# ArduinoRgbController.net
KiCad netlist of a schematic drawn in EAGLE
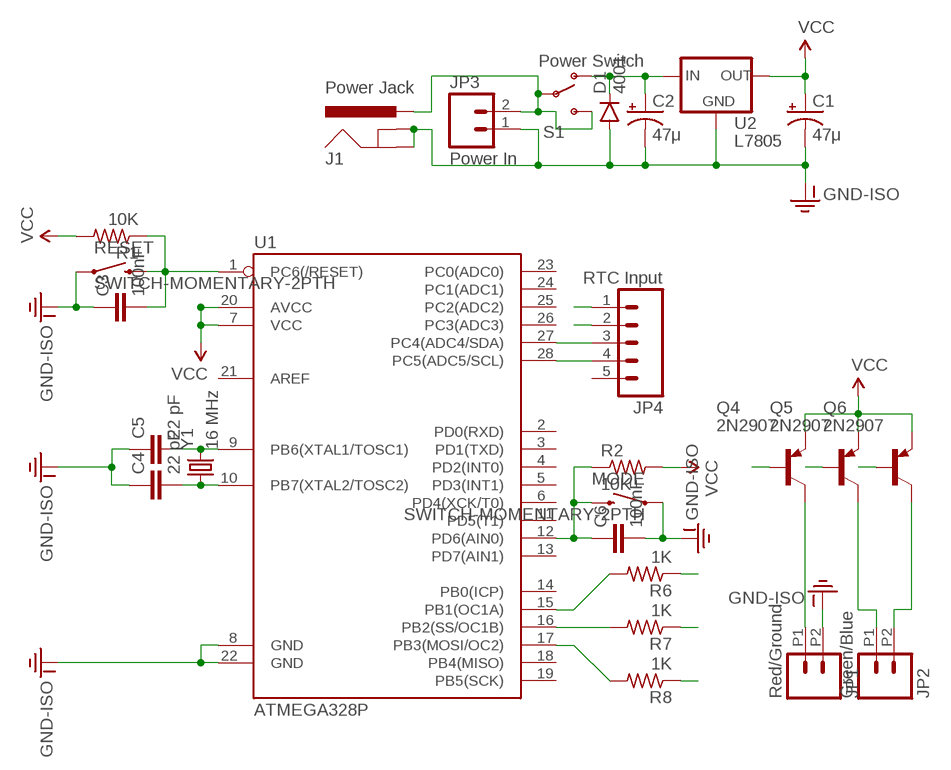
[diagram p0: schematic, sheet 1]

(export (version "E")
  (design (tool "Eeschema 10.0.6"))
  (components
    (comp (ref "C1")
      (value "47μ")
      (footprint "eagle-import:ELECTROLYTIC_CAP")
      (libsource (lib "eagle-import") (part "ELECTROLYTIC_CAP2.54MM"))
    )
    (comp (ref "C2")
      (value "47μ")
      (footprint "eagle-import:ELECTROLYTIC_CAP")
      (libsource (lib "eagle-import") (part "ELECTROLYTIC_CAP2.54MM"))
    )
    (comp (ref "C3")
      (value "100nF")
      (footprint "eagle-import:CAP-PTH-SMALL")
      (libsource (lib "eagle-import") (part "CAPPTH"))
    )
    (comp (ref "C4")
      (value "22 pF")
      (footprint "eagle-import:CAP-PTH-SMALL")
      (libsource (lib "eagle-import") (part "CAPPTH"))
    )
    (comp (ref "C5")
      (value "22 pF")
      (footprint "eagle-import:CAP-PTH-SMALL")
      (libsource (lib "eagle-import") (part "CAPPTH"))
    )
    (comp (ref "C6")
      (value "100nF")
      (footprint "eagle-import:CAP-PTH-SMALL")
      (libsource (lib "eagle-import") (part "CAPPTH"))
    )
    (comp (ref "D1")
      (value "4001")
      (footprint "eagle-import:DIODE-1N4001")
      (libsource (lib "eagle-import") (part "DIODEPTH"))
    )
    (comp (ref "J1")
      (value "Power Jack")
      (footprint "eagle-import:POWER_JACK")
      (libsource (lib "eagle-import") (part "POWER_JACK{dblquote}"))
    )
    (comp (ref "JP1")
      (value "Red/Ground")
      (footprint "eagle-import:1X02_2.54_SCREWTERM")
      (libsource (lib "eagle-import") (part "M022.54MM_SCREWTERM"))
    )
    (comp (ref "JP2")
      (value "Green/Blue")
      (footprint "eagle-import:1X02_2.54_SCREWTERM")
      (libsource (lib "eagle-import") (part "M022.54MM_SCREWTERM"))
    )
    (comp (ref "JP3")
      (value "Power In")
      (footprint "eagle-import:SCREWTERMINAL-5MM-2")
      (libsource (lib "eagle-import") (part "M025MM"))
    )
    (comp (ref "JP4")
      (value "RTC Input")
      (footprint "eagle-import:1X05_LONGPADS")
      (libsource (lib "eagle-import") (part "M05PTH_LONGPADS"))
    )
    (comp (ref "MODE")
      (value "SWITCH-MOMENTARY-2PTH")
      (footprint "eagle-import:TACTILE-PTH")
      (libsource (lib "eagle-import") (part "SWITCH-MOMENTARY-2PTH"))
    )
    (comp (ref "Q4")
      (value "2N2907")
      (footprint "eagle-import:TO92-EBC-OVAL")
      (libsource (lib "eagle-import") (part "2N2907"))
    )
    (comp (ref "Q5")
      (value "2N2907")
      (footprint "eagle-import:TO92-EBC-OVAL")
      (libsource (lib "eagle-import") (part "2N2907"))
    )
    (comp (ref "Q6")
      (value "2N2907")
      (footprint "eagle-import:TO92-EBC-OVAL")
      (libsource (lib "eagle-import") (part "2N2907"))
    )
    (comp (ref "R1")
      (value "10K")
      (footprint "eagle-import:0207_9")
      (libsource (lib "eagle-import") (part "R-US_0207/9"))
    )
    (comp (ref "R2")
      (value "10K")
      (footprint "eagle-import:0207_9")
      (libsource (lib "eagle-import") (part "R-US_0207/9"))
    )
    (comp (ref "R6")
      (value "1K")
      (footprint "eagle-import:0207_9")
      (libsource (lib "eagle-import") (part "R-US_0207/9"))
    )
    (comp (ref "R7")
      (value "1K")
      (footprint "eagle-import:0207_9")
      (libsource (lib "eagle-import") (part "R-US_0207/9"))
    )
    (comp (ref "R8")
      (value "1K")
      (footprint "eagle-import:0207_9")
      (libsource (lib "eagle-import") (part "R-US_0207/9"))
    )
    (comp (ref "RESET")
      (value "SWITCH-MOMENTARY-2PTH")
      (footprint "eagle-import:TACTILE-PTH")
      (libsource (lib "eagle-import") (part "SWITCH-MOMENTARY-2PTH"))
    )
    (comp (ref "S1")
      (value "Power Switch")
      (footprint "eagle-import:SWITCH-SPDT")
      (libsource (lib "eagle-import") (part "SWITCH-SPDTPTH"))
    )
    (comp (ref "U1")
      (value "ATMEGA328P")
      (footprint "eagle-import:DIL28-3")
      (libsource (lib "eagle-import") (part "ATMEGA328P_PDIP"))
    )
    (comp (ref "U2")
      (value "L7805")
      (footprint "eagle-import:78XXL")
      (libsource (lib "eagle-import") (part "V_REG_78XXSIDE"))
    )
    (comp (ref "Y1")
      (value "16 MHz")
      (footprint "eagle-import:HC49US")
      (libsource (lib "eagle-import") (part "CRYSTALHC49US"))
    )
  )
  (nets
    (net (code "1") (name "/BLUE") (class "Default")
      (node (ref "Q6") (pin "B") (pinfunction "B_B") (pintype "passive"))
      (node (ref "R8") (pin "1") (pinfunction "1_1") (pintype "passive"))
    )
    (net (code "2") (name "/GREEN") (class "Default")
      (node (ref "Q5") (pin "B") (pinfunction "B_B") (pintype "passive"))
      (node (ref "R7") (pin "1") (pinfunction "1_1") (pintype "passive"))
    )
    (net (code "3") (name "/RED") (class "Default")
      (node (ref "Q4") (pin "B") (pinfunction "B_B") (pintype "passive"))
      (node (ref "R6") (pin "1") (pinfunction "1_1") (pintype "passive"))
    )
    (net (code "4") (name "GND-ISO") (class "Default")
      (node (ref "C1") (pin "-") (pinfunction "-_-") (pintype "passive"))
      (node (ref "C2") (pin "-") (pinfunction "-_-") (pintype "passive"))
      (node (ref "C3") (pin "1") (pinfunction "1_1") (pintype "passive"))
      (node (ref "C4") (pin "1") (pinfunction "1_1") (pintype "passive"))
      (node (ref "C5") (pin "1") (pinfunction "1_1") (pintype "passive"))
      (node (ref "C6") (pin "2") (pinfunction "2_2") (pintype "passive"))
      (node (ref "D1") (pin "A") (pinfunction "A_A") (pintype "passive"))
      (node (ref "J1") (pin "GND") (pinfunction "GND_GND") (pintype "bidirectional"))
      (node (ref "J1") (pin "GNDBREAK") (pinfunction "GNDBREAK_GNDBREAK") (pintype "bidirectional"))
      (node (ref "JP1") (pin "P2") (pinfunction "2_P2") (pintype "passive"))
      (node (ref "JP3") (pin "1") (pinfunction "1_1") (pintype "passive"))
      (node (ref "JP4") (pin "1") (pinfunction "1_1") (pintype "passive"))
      (node (ref "MODE") (pin "1") (pinfunction "1_1") (pintype "passive"))
      (node (ref "RESET") (pin "1") (pinfunction "1_1") (pintype "passive"))
      (node (ref "U1") (pin "22") (pinfunction "GND_22") (pintype "bidirectional"))
      (node (ref "U1") (pin "8") (pinfunction "GND_8") (pintype "bidirectional"))
      (node (ref "U2") (pin "GND") (pinfunction "GND_GND") (pintype "input"))
    )
    (net (code "5") (name "Net-(JP1-1)") (class "Default")
      (node (ref "JP1") (pin "P1") (pinfunction "1_P1") (pintype "passive"))
      (node (ref "Q4") (pin "C") (pinfunction "C_C") (pintype "passive"))
    )
    (net (code "6") (name "Net-(JP2-1)") (class "Default")
      (node (ref "JP2") (pin "P1") (pinfunction "1_P1") (pintype "passive"))
      (node (ref "Q5") (pin "C") (pinfunction "C_C") (pintype "passive"))
    )
    (net (code "7") (name "Net-(JP2-2)") (class "Default")
      (node (ref "JP2") (pin "P2") (pinfunction "2_P2") (pintype "passive"))
      (node (ref "Q6") (pin "C") (pinfunction "C_C") (pintype "passive"))
    )
    (net (code "8") (name "Net-(MODE-2)") (class "Default")
      (node (ref "C6") (pin "1") (pinfunction "1_1") (pintype "passive"))
      (node (ref "MODE") (pin "3") (pinfunction "2_3") (pintype "passive"))
      (node (ref "R2") (pin "1") (pinfunction "1_1") (pintype "passive"))
      (node (ref "U1") (pin "12") (pinfunction "PD6(AIN0)_12") (pintype "bidirectional"))
    )
    (net (code "9") (name "Net-(RESET-2)") (class "Default")
      (node (ref "C3") (pin "2") (pinfunction "2_2") (pintype "passive"))
      (node (ref "R1") (pin "1") (pinfunction "1_1") (pintype "passive"))
      (node (ref "RESET") (pin "3") (pinfunction "2_3") (pintype "passive"))
      (node (ref "U1") (pin "1") (pinfunction "PC6(/RESET)_1") (pintype "bidirectional"))
    )
    (net (code "10") (name "Net-(S1-O)") (class "Default")
      (node (ref "C2") (pin "+") (pinfunction "+_+") (pintype "passive"))
      (node (ref "D1") (pin "C") (pinfunction "C_C") (pintype "passive"))
      (node (ref "S1") (pin "1") (pinfunction "O_1") (pintype "passive"))
      (node (ref "U2") (pin "IN") (pinfunction "IN_IN") (pintype "input"))
    )
    (net (code "11") (name "Net-(S1-P)") (class "Default")
      (node (ref "J1") (pin "PWR") (pinfunction "PWR_PWR") (pintype "bidirectional"))
      (node (ref "JP3") (pin "2") (pinfunction "2_2") (pintype "passive"))
      (node (ref "S1") (pin "2") (pinfunction "P_2") (pintype "passive"))
      (node (ref "S1") (pin "3") (pinfunction "S_3") (pintype "passive"))
    )
    (net (code "12") (name "Net-(U1-PB1(OC1A))") (class "Default")
      (node (ref "R6") (pin "2") (pinfunction "2_2") (pintype "passive"))
      (node (ref "U1") (pin "15") (pinfunction "PB1(OC1A)_15") (pintype "bidirectional"))
    )
    (net (code "13") (name "Net-(U1-PB2(SS{slash}OC1B))") (class "Default")
      (node (ref "R7") (pin "2") (pinfunction "2_2") (pintype "passive"))
      (node (ref "U1") (pin "16") (pinfunction "PB2(SS/OC1B)_16") (pintype "bidirectional"))
    )
    (net (code "14") (name "Net-(U1-PB3(MOSI{slash}OC2))") (class "Default")
      (node (ref "R8") (pin "2") (pinfunction "2_2") (pintype "passive"))
      (node (ref "U1") (pin "17") (pinfunction "PB3(MOSI/OC2)_17") (pintype "bidirectional"))
    )
    (net (code "15") (name "Net-(U1-PB6(XTAL1{slash}TOSC1))") (class "Default")
      (node (ref "C5") (pin "2") (pinfunction "2_2") (pintype "passive"))
      (node (ref "U1") (pin "9") (pinfunction "PB6(XTAL1/TOSC1)_9") (pintype "bidirectional"))
      (node (ref "Y1") (pin "2") (pinfunction "2_2") (pintype "passive"))
    )
    (net (code "16") (name "Net-(U1-PB7(XTAL2{slash}TOSC2))") (class "Default")
      (node (ref "C4") (pin "2") (pinfunction "2_2") (pintype "passive"))
      (node (ref "U1") (pin "10") (pinfunction "PB7(XTAL2/TOSC2)_10") (pintype "bidirectional"))
      (node (ref "Y1") (pin "1") (pinfunction "1_1") (pintype "passive"))
    )
    (net (code "17") (name "Net-(U1-PC4(ADC4{slash}SDA))") (class "Default")
      (node (ref "JP4") (pin "3") (pinfunction "3_3") (pintype "passive"))
      (node (ref "U1") (pin "27") (pinfunction "PC4(ADC4/SDA)_27") (pintype "bidirectional"))
    )
    (net (code "18") (name "Net-(U1-PC5(ADC5{slash}SCL))") (class "Default")
      (node (ref "JP4") (pin "4") (pinfunction "4_4") (pintype "passive"))
      (node (ref "U1") (pin "28") (pinfunction "PC5(ADC5/SCL)_28") (pintype "bidirectional"))
    )
    (net (code "19") (name "VCC") (class "Default")
      (node (ref "C1") (pin "+") (pinfunction "+_+") (pintype "passive"))
      (node (ref "JP4") (pin "2") (pinfunction "2_2") (pintype "passive"))
      (node (ref "Q4") (pin "E") (pinfunction "E_E") (pintype "passive"))
      (node (ref "Q5") (pin "E") (pinfunction "E_E") (pintype "passive"))
      (node (ref "Q6") (pin "E") (pinfunction "E_E") (pintype "passive"))
      (node (ref "R1") (pin "2") (pinfunction "2_2") (pintype "passive"))
      (node (ref "R2") (pin "2") (pinfunction "2_2") (pintype "passive"))
      (node (ref "U1") (pin "20") (pinfunction "AVCC_20") (pintype "bidirectional"))
      (node (ref "U1") (pin "7") (pinfunction "VCC_7") (pintype "bidirectional"))
      (node (ref "U2") (pin "OUT") (pinfunction "OUT_OUT") (pintype "passive"))
    )
    (net (code "20") (name "unconnected-(JP4-Pad5)") (class "Default")
      (node (ref "JP4") (pin "5") (pinfunction "5_5") (pintype "passive"))
    )
    (net (code "21") (name "unconnected-(U1-AREF-Pad21)") (class "Default")
      (node (ref "U1") (pin "21") (pinfunction "AREF_21") (pintype "bidirectional"))
    )
    (net (code "22") (name "unconnected-(U1-PB0(ICP)-Pad14)") (class "Default")
      (node (ref "U1") (pin "14") (pinfunction "PB0(ICP)_14") (pintype "bidirectional"))
    )
    (net (code "23") (name "unconnected-(U1-PB4(MISO)-Pad18)") (class "Default")
      (node (ref "U1") (pin "18") (pinfunction "PB4(MISO)_18") (pintype "bidirectional"))
    )
    (net (code "24") (name "unconnected-(U1-PB5(SCK)-Pad19)") (class "Default")
      (node (ref "U1") (pin "19") (pinfunction "PB5(SCK)_19") (pintype "bidirectional"))
    )
    (net (code "25") (name "unconnected-(U1-PC0(ADC0)-Pad23)") (class "Default")
      (node (ref "U1") (pin "23") (pinfunction "PC0(ADC0)_23") (pintype "bidirectional"))
    )
    (net (code "26") (name "unconnected-(U1-PC1(ADC1)-Pad24)") (class "Default")
      (node (ref "U1") (pin "24") (pinfunction "PC1(ADC1)_24") (pintype "bidirectional"))
    )
    (net (code "27") (name "unconnected-(U1-PC2(ADC2)-Pad25)") (class "Default")
      (node (ref "U1") (pin "25") (pinfunction "PC2(ADC2)_25") (pintype "bidirectional"))
    )
    (net (code "28") (name "unconnected-(U1-PC3(ADC3)-Pad26)") (class "Default")
      (node (ref "U1") (pin "26") (pinfunction "PC3(ADC3)_26") (pintype "bidirectional"))
    )
    (net (code "29") (name "unconnected-(U1-PD0(RXD)-Pad2)") (class "Default")
      (node (ref "U1") (pin "2") (pinfunction "PD0(RXD)_2") (pintype "bidirectional"))
    )
    (net (code "30") (name "unconnected-(U1-PD1(TXD)-Pad3)") (class "Default")
      (node (ref "U1") (pin "3") (pinfunction "PD1(TXD)_3") (pintype "bidirectional"))
    )
    (net (code "31") (name "unconnected-(U1-PD2(INT0)-Pad4)") (class "Default")
      (node (ref "U1") (pin "4") (pinfunction "PD2(INT0)_4") (pintype "bidirectional"))
    )
    (net (code "32") (name "unconnected-(U1-PD3(INT1)-Pad5)") (class "Default")
      (node (ref "U1") (pin "5") (pinfunction "PD3(INT1)_5") (pintype "bidirectional"))
    )
    (net (code "33") (name "unconnected-(U1-PD4(XCK{slash}T0)-Pad6)") (class "Default")
      (node (ref "U1") (pin "6") (pinfunction "PD4(XCK/T0)_6") (pintype "bidirectional"))
    )
    (net (code "34") (name "unconnected-(U1-PD5(T1)-Pad11)") (class "Default")
      (node (ref "U1") (pin "11") (pinfunction "PD5(T1)_11") (pintype "bidirectional"))
    )
    (net (code "35") (name "unconnected-(U1-PD7(AIN1)-Pad13)") (class "Default")
      (node (ref "U1") (pin "13") (pinfunction "PD7(AIN1)_13") (pintype "bidirectional"))
    )
  )
)
